# medusa-charger.net
KiCad netlist of a schematic drawn in Altium Designer
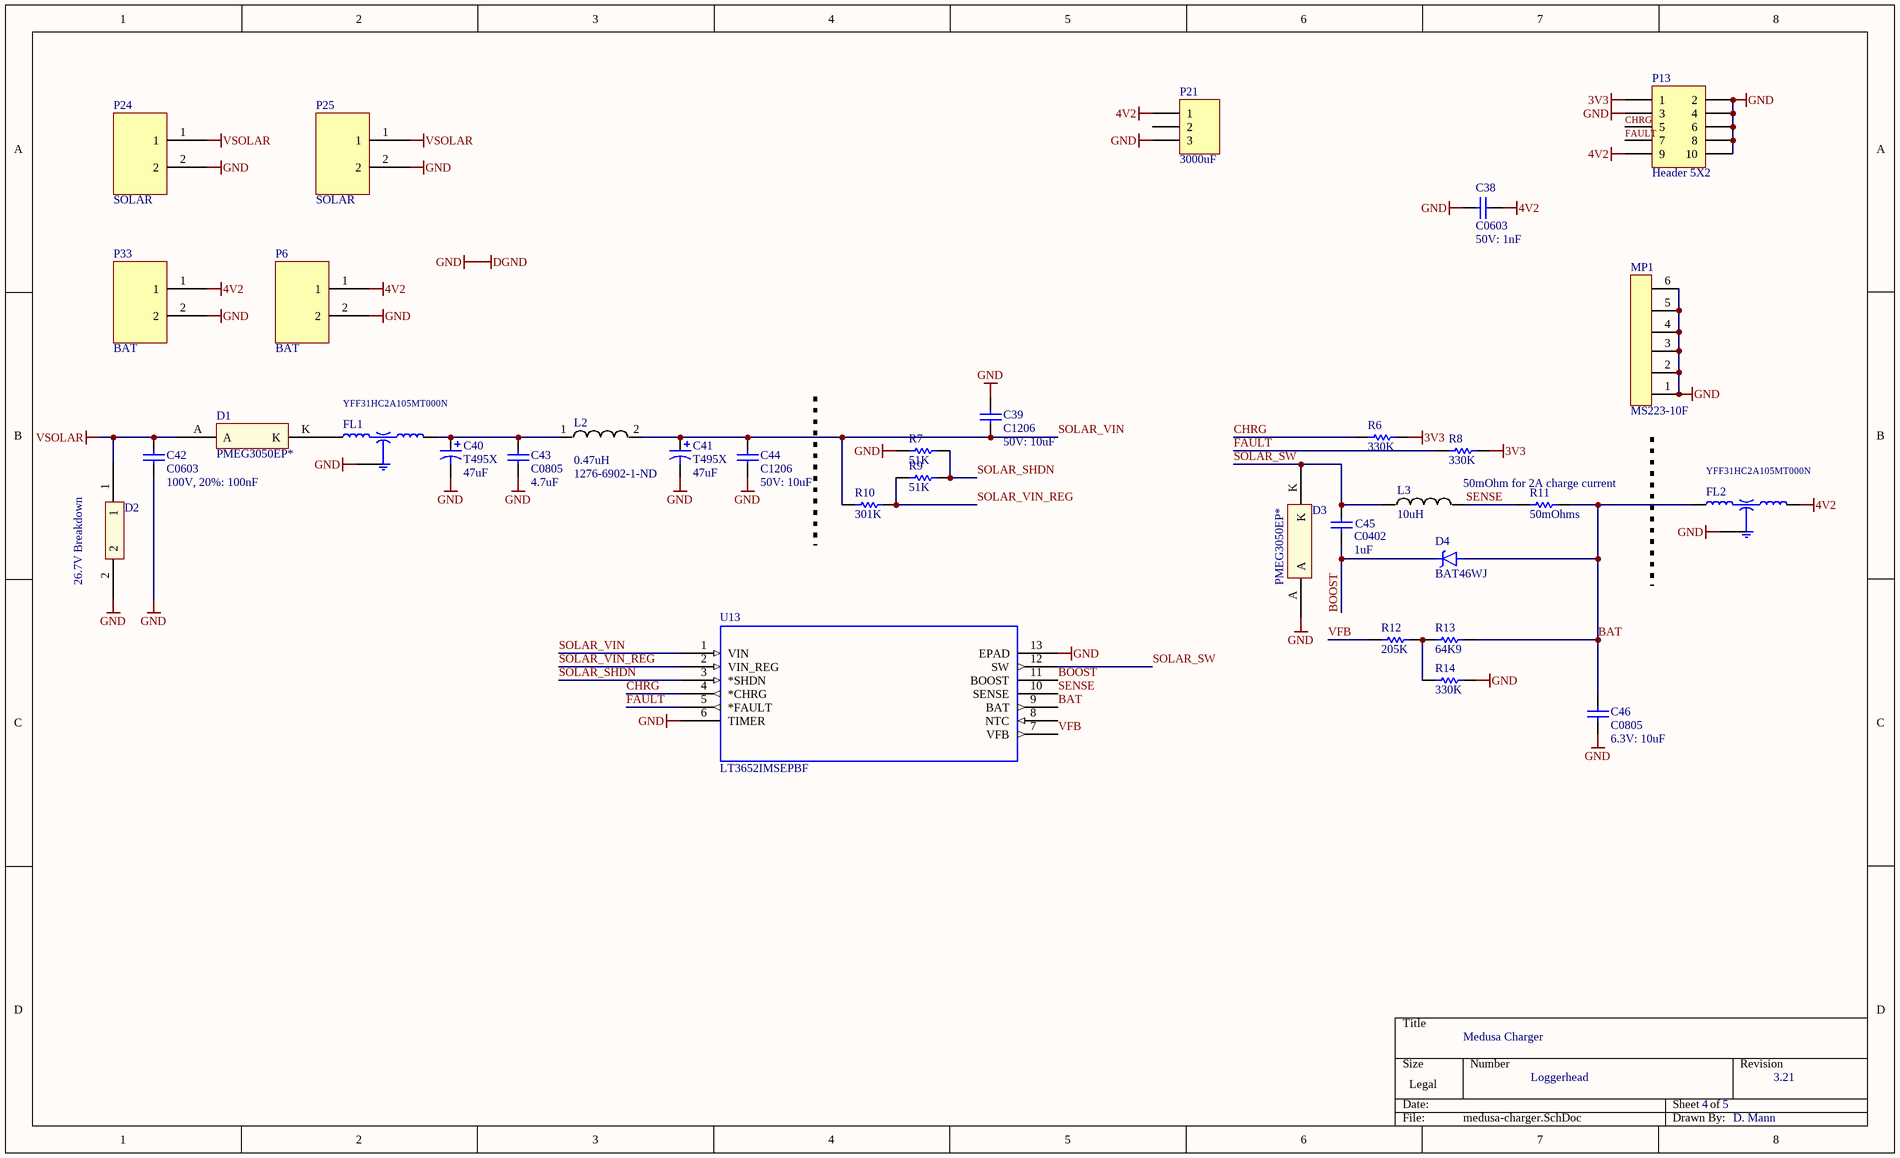
[diagram p0: medusa-charger.SchDoc]

(export (version "E")
  (design (tool "Eeschema 10.0.6"))
  (components
    (comp (ref "C38")
      (value "C0603")
      (footprint "0603")
      (description "Ceramic Chip Capacitor - Standard")
      (fields (field (name "50V") "1nF") (field (name "PUBLISHER") "Altium Limited"))
      (libsource (lib "KEMET Chip Capacitor") (part "C0603"))
    )
    (comp (ref "C39")
      (value "C1206")
      (footprint "1206")
      (description "Ceramic Chip Capacitor - Standard")
      (fields (field (name "50V") "10uF") (field (name "PUBLISHER") "Altium Limited"))
      (libsource (lib "KEMET Chip Capacitor") (part "C1206"))
    )
    (comp (ref "C40")
      (value "T495X")
      (footprint "X")
      (description "Solid Tantalum Chip Capacitor, Standard T495 Series - 35V 10%")
      (fields (field (name "ALTIUM_VALUE") "47uF") (field (name "PUBLISHER") "Altium Limited"))
      (libsource (lib "KEMET Chip Capacitor") (part "T495X"))
    )
    (comp (ref "C41")
      (value "T495X")
      (footprint "X")
      (description "Solid Tantalum Chip Capacitor, Standard T495 Series - 35V 10%")
      (fields (field (name "ALTIUM_VALUE") "47uF") (field (name "PUBLISHER") "Altium Limited"))
      (libsource (lib "KEMET Chip Capacitor") (part "T495X"))
    )
    (comp (ref "C42")
      (value "C0603")
      (footprint "0603")
      (description "100V 20%")
      (fields (field (name "100V, 20%") "100nF") (field (name "PUBLISHER") "Altium Limited"))
      (libsource (lib "KEMET Chip Capacitor") (part "C0603"))
    )
    (comp (ref "C43")
      (value "C0805")
      (footprint "0805")
      (description "Ceramic Chip Capacitor - Standard")
      (fields (field (name "ALTIUM_VALUE") "4.7uF") (field (name "PUBLISHER") "Altium Limited"))
      (libsource (lib "KEMET Chip Capacitor") (part "C0805"))
    )
    (comp (ref "C44")
      (value "C1206")
      (footprint "1206")
      (description "Ceramic Chip Capacitor - Standard")
      (fields (field (name "50V") "10uF") (field (name "PUBLISHER") "Altium Limited"))
      (libsource (lib "KEMET Chip Capacitor") (part "C1206"))
    )
    (comp (ref "C45")
      (value "C0402")
      (footprint "0402")
      (description "Ceramic Chip Capacitor - Standard")
      (fields (field (name "ALTIUM_VALUE") "1uF") (field (name "PUBLISHER") "Altium Limited"))
      (libsource (lib "KEMET Chip Capacitor") (part "C0402"))
    )
    (comp (ref "C46")
      (value "C0805")
      (footprint "0805")
      (description "Ceramic Chip Capacitor - Standard")
      (fields (field (name "6.3V") "10uF") (field (name "PUBLISHER") "Altium Limited"))
      (libsource (lib "KEMET Chip Capacitor") (part "C0805"))
    )
    (comp (ref "D1")
      (value "PMEG3050EP*")
      (footprint "Diode_PMEG3050EP")
      (libsource (lib "Loggerhead") (part "Diode_PMEG3050EP"))
    )
    (comp (ref "D2")
      (value "26.7V Breakdown")
      (footprint "SMBJ24CA")
      (libsource (lib "Loggerhead") (part "SMBJ24CA"))
    )
    (comp (ref "D3")
      (value "PMEG3050EP*")
      (footprint "Diode_PMEG3050EP")
      (libsource (lib "") (part "Diode_PMEG3050EP_1"))
    )
    (comp (ref "D4")
      (value "BAT46WJ")
      (footprint "SOD-323")
      (description "Diode Schottky 100V 250mA (DC) Surface Mount SOD-323F")
      (fields (field (name "MF") "NXP Semiconductors"))
      (libsource (lib "BAT46WJ") (part "BAT46WJ"))
    )
    (comp (ref "FL1")
      (value "YFF31HC2A105MT000N")
      (footprint "FIL_YFF31HC2A105MT000N")
      (description "1ÂµF Feed Through Capacitor 100V 6A 5mOhm 1206 (3216 Metric), 4 PC Pad")
      (fields (field (name "MF") "TDK"))
      (libsource (lib "YFF31HC2A105MT000N") (part "YFF31HC2A105MT000N"))
    )
    (comp (ref "FL2")
      (value "YFF31HC2A105MT000N")
      (footprint "FIL_YFF31HC2A105MT000N")
      (description "1ÂµF Feed Through Capacitor 100V 6A 5mOhm 1206 (3216 Metric), 4 PC Pad")
      (fields (field (name "MF") "TDK"))
      (libsource (lib "YFF31HC2A105MT000N") (part "YFF31HC2A105MT000N"))
    )
    (comp (ref "L2")
      (value "0.47uH")
      (footprint "Inductor2016")
      (fields
        (field (name "SUPPLIER PART NUMBER 1") "1276-6902-1-ND")
        (field (name "Comment") "Inductor2016")
      )
      (libsource (lib "Loggerhead") (part "Inductor2016"))
    )
    (comp (ref "L3")
      (value "10uH")
      (footprint "Inductor0630CDMCD")
      (libsource (lib "Loggerhead") (part "Inductor_0630CDMCD"))
    )
    (comp (ref "MP1")
      (value "MS223-10F")
      (footprint "MS223-10F")
      (description "RF Shield")
      (libsource (lib "Loggerhead") (part "MS223-10F"))
    )
    (comp (ref "P6")
      (value "BAT")
      (footprint "HDR_2x1_2mm")
      (libsource (lib "Loggerhead") (part "HDR_2x1_2mm"))
    )
    (comp (ref "P13")
      (value "Header 5X2")
      (footprint "HDR2X5")
      (description "Header, 5-Pin, Dual row")
      (fields (field (name "PUBLISHER") "Altium Limited"))
      (libsource (lib "Miscellaneous Connectors") (part "Header 5X2"))
    )
    (comp (ref "P21")
      (value "3000uF")
      (footprint "HDR1X3")
      (description "Header, 3-Pin")
      (fields (field (name "PUBLISHER") "Altium Limited"))
      (libsource (lib "Miscellaneous Connectors") (part "Header 3"))
    )
    (comp (ref "P24")
      (value "SOLAR")
      (footprint "HDR_2x1_2mm")
      (libsource (lib "Loggerhead") (part "HDR_2x1_2mm"))
    )
    (comp (ref "P25")
      (value "SOLAR")
      (footprint "HDR_2x1_2mm")
      (libsource (lib "Loggerhead") (part "HDR_2x1_2mm"))
    )
    (comp (ref "P33")
      (value "BAT")
      (footprint "HDR_2x1_2mm")
      (libsource (lib "Loggerhead") (part "HDR_2x1_2mm"))
    )
    (comp (ref "R6")
      (value "330K")
      (footprint "3-0603")
      (fields (field (name "PUBLISHER") "Altium Limited"))
      (libsource (lib "Panasonic Resistor") (part "ERJ3EK"))
    )
    (comp (ref "R7")
      (value "51K")
      (footprint "3-0603")
      (fields (field (name "PUBLISHER") "Altium Limited"))
      (libsource (lib "Panasonic Resistor") (part "ERJ3EK"))
    )
    (comp (ref "R8")
      (value "330K")
      (footprint "3-0603")
      (fields (field (name "PUBLISHER") "Altium Limited"))
      (libsource (lib "Panasonic Resistor") (part "ERJ3EK"))
    )
    (comp (ref "R9")
      (value "51K")
      (footprint "3-0603")
      (fields (field (name "PUBLISHER") "Altium Limited"))
      (libsource (lib "Panasonic Resistor") (part "ERJ3EK"))
    )
    (comp (ref "R10")
      (value "301K")
      (footprint "3-0603")
      (fields (field (name "PUBLISHER") "Altium Limited"))
      (libsource (lib "Panasonic Resistor") (part "ERJ3EK"))
    )
    (comp (ref "R11")
      (value "50mOhms")
      (footprint "8-1206")
      (description "Precision Thick Film Chip Resistor, 10 Ohm to 2.2M Ohm Range, 1% Tolerance, 1206 Size, 0.125 W")
      (fields (field (name "PUBLISHER") "Altium Limited"))
      (libsource (lib "Panasonic Resistor") (part "ERJ8EN"))
    )
    (comp (ref "R12")
      (value "205K")
      (footprint "3-0603")
      (fields (field (name "PUBLISHER") "Altium Limited"))
      (libsource (lib "Panasonic Resistor") (part "ERJ3EK"))
    )
    (comp (ref "R13")
      (value "64K9")
      (footprint "3-0603")
      (fields (field (name "PUBLISHER") "Altium Limited"))
      (libsource (lib "Panasonic Resistor") (part "ERJ3EK"))
    )
    (comp (ref "R14")
      (value "330K")
      (footprint "3-0603")
      (fields (field (name "PUBLISHER") "Altium Limited"))
      (libsource (lib "Panasonic Resistor") (part "ERJ3EK"))
    )
    (comp (ref "U13")
      (value "LT3652IMSEPBF")
      (footprint "MSOP-12_MSE")
      (description "Battery Charger Li-Ion 2000mA 4.2V Automotive 12-Pin MSOP EP Tube")
      (fields (field (name "MP") "LT3652IMSE#PBF") (field (name "DIGI-KEY_PART_NUMBER") "LT3652IMSE#PBF-ND"))
      (libsource (lib "LT3652IMSEPBF") (part "LT3652IMSEPBF"))
    )
  )
  (nets
    (net (code "1") (name "/BAT") (class "Default")
      (node (ref "C46") (pin "2") (pinfunction "2_2") (pintype "passive"))
      (node (ref "D4") (pin "A") (pinfunction "A_A") (pintype "passive"))
      (node (ref "FL2") (pin "1") (pinfunction "IN/OUT_1") (pintype "passive"))
      (node (ref "R11") (pin "2") (pinfunction "2_2") (pintype "passive"))
      (node (ref "R13") (pin "1") (pinfunction "1_1") (pintype "passive"))
      (node (ref "U13") (pin "9") (pinfunction "BAT_9") (pintype "output"))
    )
    (net (code "2") (name "/BOOST") (class "Default")
      (node (ref "C45") (pin "1") (pinfunction "1_1") (pintype "passive"))
      (node (ref "D4") (pin "C") (pinfunction "C_C") (pintype "passive"))
      (node (ref "U13") (pin "11") (pinfunction "BOOST_11") (pintype "passive"))
    )
    (net (code "3") (name "/CHRG") (class "Default")
      (node (ref "P13") (pin "5") (pinfunction "5_5") (pintype "passive"))
      (node (ref "R6") (pin "2") (pinfunction "2_2") (pintype "passive"))
      (node (ref "U13") (pin "4") (pinfunction "*CHRG_4") (pintype "output"))
    )
    (net (code "4") (name "/FAULT") (class "Default")
      (node (ref "P13") (pin "7") (pinfunction "7_7") (pintype "passive"))
      (node (ref "R8") (pin "2") (pinfunction "2_2") (pintype "passive"))
      (node (ref "U13") (pin "5") (pinfunction "*FAULT_5") (pintype "output"))
    )
    (net (code "5") (name "/SENSE") (class "Default")
      (node (ref "L3") (pin "2") (pinfunction "2_2") (pintype "passive"))
      (node (ref "R11") (pin "1") (pinfunction "1_1") (pintype "passive"))
      (node (ref "U13") (pin "10") (pinfunction "SENSE_10") (pintype "passive"))
    )
    (net (code "6") (name "/SOLAR_SHDN") (class "Default")
      (node (ref "R7") (pin "2") (pinfunction "2_2") (pintype "passive"))
      (node (ref "R9") (pin "2") (pinfunction "2_2") (pintype "passive"))
      (node (ref "U13") (pin "3") (pinfunction "*SHDN_3") (pintype "input"))
    )
    (net (code "7") (name "/SOLAR_SW") (class "Default")
      (node (ref "C45") (pin "2") (pinfunction "2_2") (pintype "passive"))
      (node (ref "D3") (pin "K") (pinfunction "K_K") (pintype "passive"))
      (node (ref "L3") (pin "1") (pinfunction "1_1") (pintype "passive"))
      (node (ref "U13") (pin "12") (pinfunction "SW_12") (pintype "output"))
    )
    (net (code "8") (name "/SOLAR_VIN") (class "Default")
      (node (ref "C39") (pin "2") (pinfunction "2_2") (pintype "passive"))
      (node (ref "C41") (pin "1") (pinfunction "1_1") (pintype "passive"))
      (node (ref "C44") (pin "2") (pinfunction "2_2") (pintype "passive"))
      (node (ref "L2") (pin "2") (pinfunction "2_2") (pintype "passive"))
      (node (ref "R10") (pin "1") (pinfunction "1_1") (pintype "passive"))
      (node (ref "U13") (pin "1") (pinfunction "VIN_1") (pintype "input"))
    )
    (net (code "9") (name "/SOLAR_VIN_REG") (class "Default")
      (node (ref "R10") (pin "2") (pinfunction "2_2") (pintype "passive"))
      (node (ref "R9") (pin "1") (pinfunction "1_1") (pintype "passive"))
      (node (ref "U13") (pin "2") (pinfunction "VIN_REG_2") (pintype "input"))
    )
    (net (code "10") (name "/VFB") (class "Default")
      (node (ref "R12") (pin "2") (pinfunction "2_2") (pintype "passive"))
      (node (ref "U13") (pin "7") (pinfunction "VFB_7") (pintype "output"))
    )
    (net (code "11") (name "3V3") (class "Default")
      (node (ref "P13") (pin "1") (pinfunction "1_1") (pintype "passive"))
      (node (ref "R6") (pin "1") (pinfunction "1_1") (pintype "passive"))
      (node (ref "R8") (pin "1") (pinfunction "1_1") (pintype "passive"))
    )
    (net (code "12") (name "4V2") (class "Default")
      (node (ref "C38") (pin "2") (pinfunction "2_2") (pintype "passive"))
      (node (ref "FL2") (pin "3") (pinfunction "OUT/IN_3") (pintype "passive"))
      (node (ref "P13") (pin "9") (pinfunction "9_9") (pintype "passive"))
      (node (ref "P21") (pin "1") (pinfunction "1_1") (pintype "passive"))
      (node (ref "P33") (pin "1") (pinfunction "1_1") (pintype "passive"))
      (node (ref "P6") (pin "1") (pinfunction "1_1") (pintype "passive"))
    )
    (net (code "13") (name "DGND") (class "Default")
      (node (ref "C38") (pin "1") (pinfunction "1_1") (pintype "passive"))
      (node (ref "C39") (pin "1") (pinfunction "1_1") (pintype "passive"))
      (node (ref "C40") (pin "2") (pinfunction "2_2") (pintype "passive"))
      (node (ref "C41") (pin "2") (pinfunction "2_2") (pintype "passive"))
      (node (ref "C42") (pin "1") (pinfunction "1_1") (pintype "passive"))
      (node (ref "C43") (pin "1") (pinfunction "1_1") (pintype "passive"))
      (node (ref "C44") (pin "1") (pinfunction "1_1") (pintype "passive"))
      (node (ref "C46") (pin "1") (pinfunction "1_1") (pintype "passive"))
      (node (ref "D2") (pin "2") (pinfunction "2_2") (pintype "passive"))
      (node (ref "D3") (pin "A") (pinfunction "A_A") (pintype "passive"))
      (node (ref "FL1") (pin "2_4") (pinfunction "GND_2_4") (pintype "power_in"))
      (node (ref "FL2") (pin "2_4") (pinfunction "GND_2_4") (pintype "power_in"))
      (node (ref "MP1") (pin "1") (pinfunction "1_1") (pintype "passive"))
      (node (ref "MP1") (pin "2") (pinfunction "2_2") (pintype "passive"))
      (node (ref "MP1") (pin "3") (pinfunction "3_3") (pintype "passive"))
      (node (ref "MP1") (pin "4") (pinfunction "4_4") (pintype "passive"))
      (node (ref "MP1") (pin "5") (pinfunction "5_5") (pintype "passive"))
      (node (ref "MP1") (pin "6") (pinfunction "6_6") (pintype "passive"))
      (node (ref "P13") (pin "10") (pinfunction "10_10") (pintype "passive"))
      (node (ref "P13") (pin "2") (pinfunction "2_2") (pintype "passive"))
      (node (ref "P13") (pin "3") (pinfunction "3_3") (pintype "passive"))
      (node (ref "P13") (pin "4") (pinfunction "4_4") (pintype "passive"))
      (node (ref "P13") (pin "6") (pinfunction "6_6") (pintype "passive"))
      (node (ref "P13") (pin "8") (pinfunction "8_8") (pintype "passive"))
      (node (ref "P21") (pin "3") (pinfunction "3_3") (pintype "passive"))
      (node (ref "P24") (pin "2") (pinfunction "2_2") (pintype "passive"))
      (node (ref "P25") (pin "2") (pinfunction "2_2") (pintype "passive"))
      (node (ref "P33") (pin "2") (pinfunction "2_2") (pintype "passive"))
      (node (ref "P6") (pin "2") (pinfunction "2_2") (pintype "passive"))
      (node (ref "R14") (pin "1") (pinfunction "1_1") (pintype "passive"))
      (node (ref "R7") (pin "1") (pinfunction "1_1") (pintype "passive"))
      (node (ref "U13") (pin "13") (pinfunction "EPAD_13") (pintype "passive"))
      (node (ref "U13") (pin "6") (pinfunction "TIMER_6") (pintype "passive"))
    )
    (net (code "14") (name "Net-(FL1-IN{slash}OUT)") (class "Default")
      (node (ref "D1") (pin "K") (pinfunction "K_K") (pintype "passive"))
      (node (ref "FL1") (pin "1") (pinfunction "IN/OUT_1") (pintype "passive"))
    )
    (net (code "15") (name "Net-(FL1-OUT{slash}IN)") (class "Default")
      (node (ref "C40") (pin "1") (pinfunction "1_1") (pintype "passive"))
      (node (ref "C43") (pin "2") (pinfunction "2_2") (pintype "passive"))
      (node (ref "FL1") (pin "3") (pinfunction "OUT/IN_3") (pintype "passive"))
      (node (ref "L2") (pin "1") (pinfunction "1_1") (pintype "passive"))
    )
    (net (code "16") (name "Net-(R12-Pad1)") (class "Default")
      (node (ref "R12") (pin "1") (pinfunction "1_1") (pintype "passive"))
      (node (ref "R13") (pin "2") (pinfunction "2_2") (pintype "passive"))
      (node (ref "R14") (pin "2") (pinfunction "2_2") (pintype "passive"))
    )
    (net (code "17") (name "VSOLAR") (class "Default")
      (node (ref "C42") (pin "2") (pinfunction "2_2") (pintype "passive"))
      (node (ref "D1") (pin "A") (pinfunction "A_A") (pintype "passive"))
      (node (ref "D2") (pin "1") (pinfunction "1_1") (pintype "passive"))
      (node (ref "P24") (pin "1") (pinfunction "1_1") (pintype "passive"))
      (node (ref "P25") (pin "1") (pinfunction "1_1") (pintype "passive"))
    )
    (net (code "18") (name "unconnected-(P21-Pad2)") (class "Default")
      (node (ref "P21") (pin "2") (pinfunction "2_2") (pintype "passive"))
    )
    (net (code "19") (name "unconnected-(U13-NTC-Pad8)") (class "Default")
      (node (ref "U13") (pin "8") (pinfunction "NTC_8") (pintype "input"))
    )
  )
)
